# cassowarii-controller.net
KiCad netlist of a schematic drawn in EAGLE
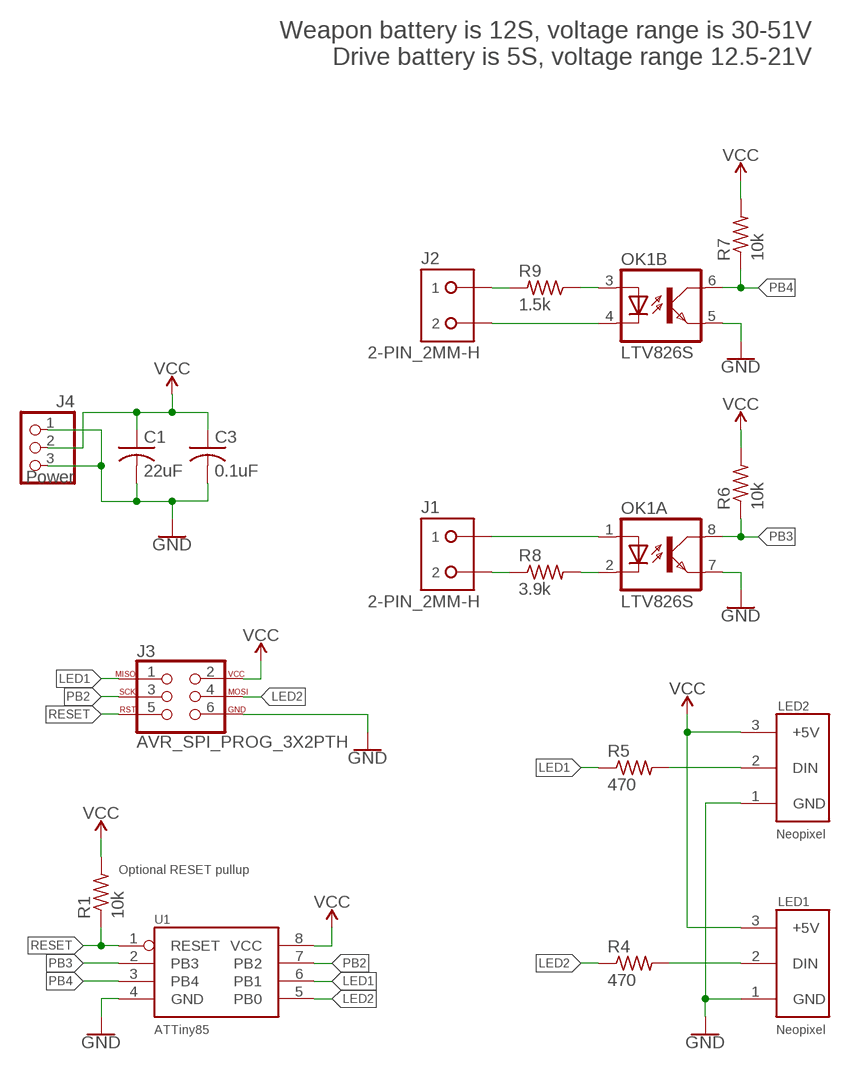
[diagram p0: schematic, sheet 1]

(export (version "E")
  (design (tool "Eeschema 10.0.6"))
  (components
    (comp (ref "C1")
      (value "22uF")
      (footprint "eagle-import:C0805")
      (libsource (lib "eagle-import") (part "C-USC0805"))
    )
    (comp (ref "C3")
      (value "0.1uF")
      (footprint "eagle-import:C0805")
      (libsource (lib "eagle-import") (part "C-USC0805"))
    )
    (comp (ref "J1")
      (value "2-PIN_2MM-H")
      (footprint "eagle-import:2MM-2-H")
      (libsource (lib "eagle-import") (part "2-PIN_2MM-H"))
    )
    (comp (ref "J2")
      (value "2-PIN_2MM-H")
      (footprint "eagle-import:2MM-2-H")
      (libsource (lib "eagle-import") (part "2-PIN_2MM-H"))
    )
    (comp (ref "J3")
      (value "AVR_SPI_PROG_3X2PTH")
      (footprint "eagle-import:2X3")
      (libsource (lib "eagle-import") (part "AVR_SPI_PROG_3X2PTH"))
    )
    (comp (ref "J4")
      (value "Power")
      (footprint "eagle-import:1X03")
      (libsource (lib "eagle-import") (part "PINHD-1X3"))
    )
    (comp (ref "LED1")
      (value "Neopixel")
      (footprint "eagle-import:2MM-3-H")
      (libsource (lib "eagle-import") (part "NEOPIXEL2MM_MOLEX"))
    )
    (comp (ref "LED2")
      (value "Neopixel")
      (footprint "eagle-import:2MM-3-H")
      (libsource (lib "eagle-import") (part "NEOPIXEL2MM_MOLEX"))
    )
    (comp (ref "OK1")
      (value "LTV826S")
      (footprint "eagle-import:DIL8-SMD")
      (libsource (lib "eagle-import") (part "LTV826S"))
    )
    (comp (ref "R1")
      (value "10k")
      (footprint "eagle-import:R0805")
      (libsource (lib "eagle-import") (part "R-US_R0805"))
    )
    (comp (ref "R4")
      (value "470")
      (footprint "eagle-import:R0805")
      (libsource (lib "eagle-import") (part "R-US_R0805"))
    )
    (comp (ref "R5")
      (value "470")
      (footprint "eagle-import:R0805")
      (libsource (lib "eagle-import") (part "R-US_R0805"))
    )
    (comp (ref "R6")
      (value "10k")
      (footprint "eagle-import:R0805")
      (libsource (lib "eagle-import") (part "R-US_R0805"))
    )
    (comp (ref "R7")
      (value "10k")
      (footprint "eagle-import:R0805")
      (libsource (lib "eagle-import") (part "R-US_R0805"))
    )
    (comp (ref "R8")
      (value "3.9k")
      (footprint "eagle-import:0207_2V")
      (libsource (lib "eagle-import") (part "R-US_0207/2V"))
    )
    (comp (ref "R9")
      (value "1.5k")
      (footprint "eagle-import:0207_2V")
      (libsource (lib "eagle-import") (part "R-US_0207/2V"))
    )
    (comp (ref "U1")
      (value "ATTiny85")
      (footprint "eagle-import:SOIC8")
      (libsource (lib "eagle-import") (part "ATTINY85SOIC8"))
    )
  )
  (nets
    (net (code "1") (name "GND") (class "Default")
      (node (ref "C1") (pin "2") (pinfunction "2_2") (pintype "passive"))
      (node (ref "C3") (pin "2") (pinfunction "2_2") (pintype "passive"))
      (node (ref "J3") (pin "6") (pinfunction "6_6") (pintype "passive"))
      (node (ref "J4") (pin "1") (pinfunction "1_1") (pintype "passive"))
      (node (ref "J4") (pin "3") (pinfunction "3_3") (pintype "passive"))
      (node (ref "LED1") (pin "1") (pinfunction "GND_1") (pintype "power_in"))
      (node (ref "LED2") (pin "1") (pinfunction "GND_1") (pintype "power_in"))
      (node (ref "OK1") (pin "5") (pinfunction "EMIT_5") (pintype "passive"))
      (node (ref "OK1") (pin "7") (pinfunction "EMIT_7") (pintype "passive"))
      (node (ref "U1") (pin "4") (pinfunction "GND_4") (pintype "power_in"))
    )
    (net (code "2") (name "LED1") (class "Default")
      (node (ref "J3") (pin "1") (pinfunction "1_1") (pintype "passive"))
      (node (ref "R5") (pin "1") (pinfunction "1_1") (pintype "passive"))
      (node (ref "U1") (pin "6") (pinfunction "PB1_6") (pintype "bidirectional"))
    )
    (net (code "3") (name "LED2") (class "Default")
      (node (ref "J3") (pin "4") (pinfunction "4_4") (pintype "passive"))
      (node (ref "R4") (pin "1") (pinfunction "1_1") (pintype "passive"))
      (node (ref "U1") (pin "5") (pinfunction "PB0_5") (pintype "bidirectional"))
    )
    (net (code "4") (name "Net-(J1-Pad2)") (class "Default")
      (node (ref "J1") (pin "2") (pinfunction "2_2") (pintype "bidirectional"))
      (node (ref "R8") (pin "1") (pinfunction "1_1") (pintype "passive"))
    )
    (net (code "5") (name "Net-(J2-Pad1)") (class "Default")
      (node (ref "J2") (pin "1") (pinfunction "1_1") (pintype "bidirectional"))
      (node (ref "R9") (pin "2") (pinfunction "2_2") (pintype "passive"))
    )
    (net (code "6") (name "Net-(LED1-DIN)") (class "Default")
      (node (ref "LED1") (pin "2") (pinfunction "DIN_2") (pintype "input"))
      (node (ref "R4") (pin "2") (pinfunction "2_2") (pintype "passive"))
    )
    (net (code "7") (name "Net-(LED2-DIN)") (class "Default")
      (node (ref "LED2") (pin "2") (pinfunction "DIN_2") (pintype "input"))
      (node (ref "R5") (pin "2") (pinfunction "2_2") (pintype "passive"))
    )
    (net (code "8") (name "Net-(OK1A-A)") (class "Default")
      (node (ref "J1") (pin "1") (pinfunction "1_1") (pintype "bidirectional"))
      (node (ref "OK1") (pin "1") (pinfunction "A_1") (pintype "passive"))
    )
    (net (code "9") (name "Net-(OK1A-C)") (class "Default")
      (node (ref "OK1") (pin "2") (pinfunction "C_2") (pintype "passive"))
      (node (ref "R8") (pin "2") (pinfunction "2_2") (pintype "passive"))
    )
    (net (code "10") (name "Net-(OK1B-A)") (class "Default")
      (node (ref "OK1") (pin "3") (pinfunction "A_3") (pintype "passive"))
      (node (ref "R9") (pin "1") (pinfunction "1_1") (pintype "passive"))
    )
    (net (code "11") (name "Net-(OK1B-C)") (class "Default")
      (node (ref "J2") (pin "2") (pinfunction "2_2") (pintype "bidirectional"))
      (node (ref "OK1") (pin "4") (pinfunction "C_4") (pintype "passive"))
    )
    (net (code "12") (name "PB2") (class "Default")
      (node (ref "J3") (pin "3") (pinfunction "3_3") (pintype "passive"))
      (node (ref "U1") (pin "7") (pinfunction "PB2_7") (pintype "bidirectional"))
    )
    (net (code "13") (name "PB3") (class "Default")
      (node (ref "OK1") (pin "8") (pinfunction "COL_8") (pintype "passive"))
      (node (ref "R6") (pin "1") (pinfunction "1_1") (pintype "passive"))
      (node (ref "U1") (pin "2") (pinfunction "PB3_2") (pintype "bidirectional"))
    )
    (net (code "14") (name "PB4") (class "Default")
      (node (ref "OK1") (pin "6") (pinfunction "COL_6") (pintype "passive"))
      (node (ref "R7") (pin "1") (pinfunction "1_1") (pintype "passive"))
      (node (ref "U1") (pin "3") (pinfunction "PB4_3") (pintype "bidirectional"))
    )
    (net (code "15") (name "RESET") (class "Default")
      (node (ref "J3") (pin "5") (pinfunction "5_5") (pintype "passive"))
      (node (ref "R1") (pin "1") (pinfunction "1_1") (pintype "passive"))
      (node (ref "U1") (pin "1") (pinfunction "RESET_1") (pintype "input"))
    )
    (net (code "16") (name "VCC") (class "Default")
      (node (ref "C1") (pin "1") (pinfunction "1_1") (pintype "passive"))
      (node (ref "C3") (pin "1") (pinfunction "1_1") (pintype "passive"))
      (node (ref "J3") (pin "2") (pinfunction "2_2") (pintype "passive"))
      (node (ref "J4") (pin "2") (pinfunction "2_2") (pintype "passive"))
      (node (ref "LED1") (pin "3") (pinfunction "+5V_3") (pintype "power_in"))
      (node (ref "LED2") (pin "3") (pinfunction "+5V_3") (pintype "power_in"))
      (node (ref "R1") (pin "2") (pinfunction "2_2") (pintype "passive"))
      (node (ref "R6") (pin "2") (pinfunction "2_2") (pintype "passive"))
      (node (ref "R7") (pin "2") (pinfunction "2_2") (pintype "passive"))
      (node (ref "U1") (pin "8") (pinfunction "VCC_8") (pintype "power_in"))
    )
  )
)
